# Schematic1.net
KiCad netlist of a schematic drawn in EAGLE
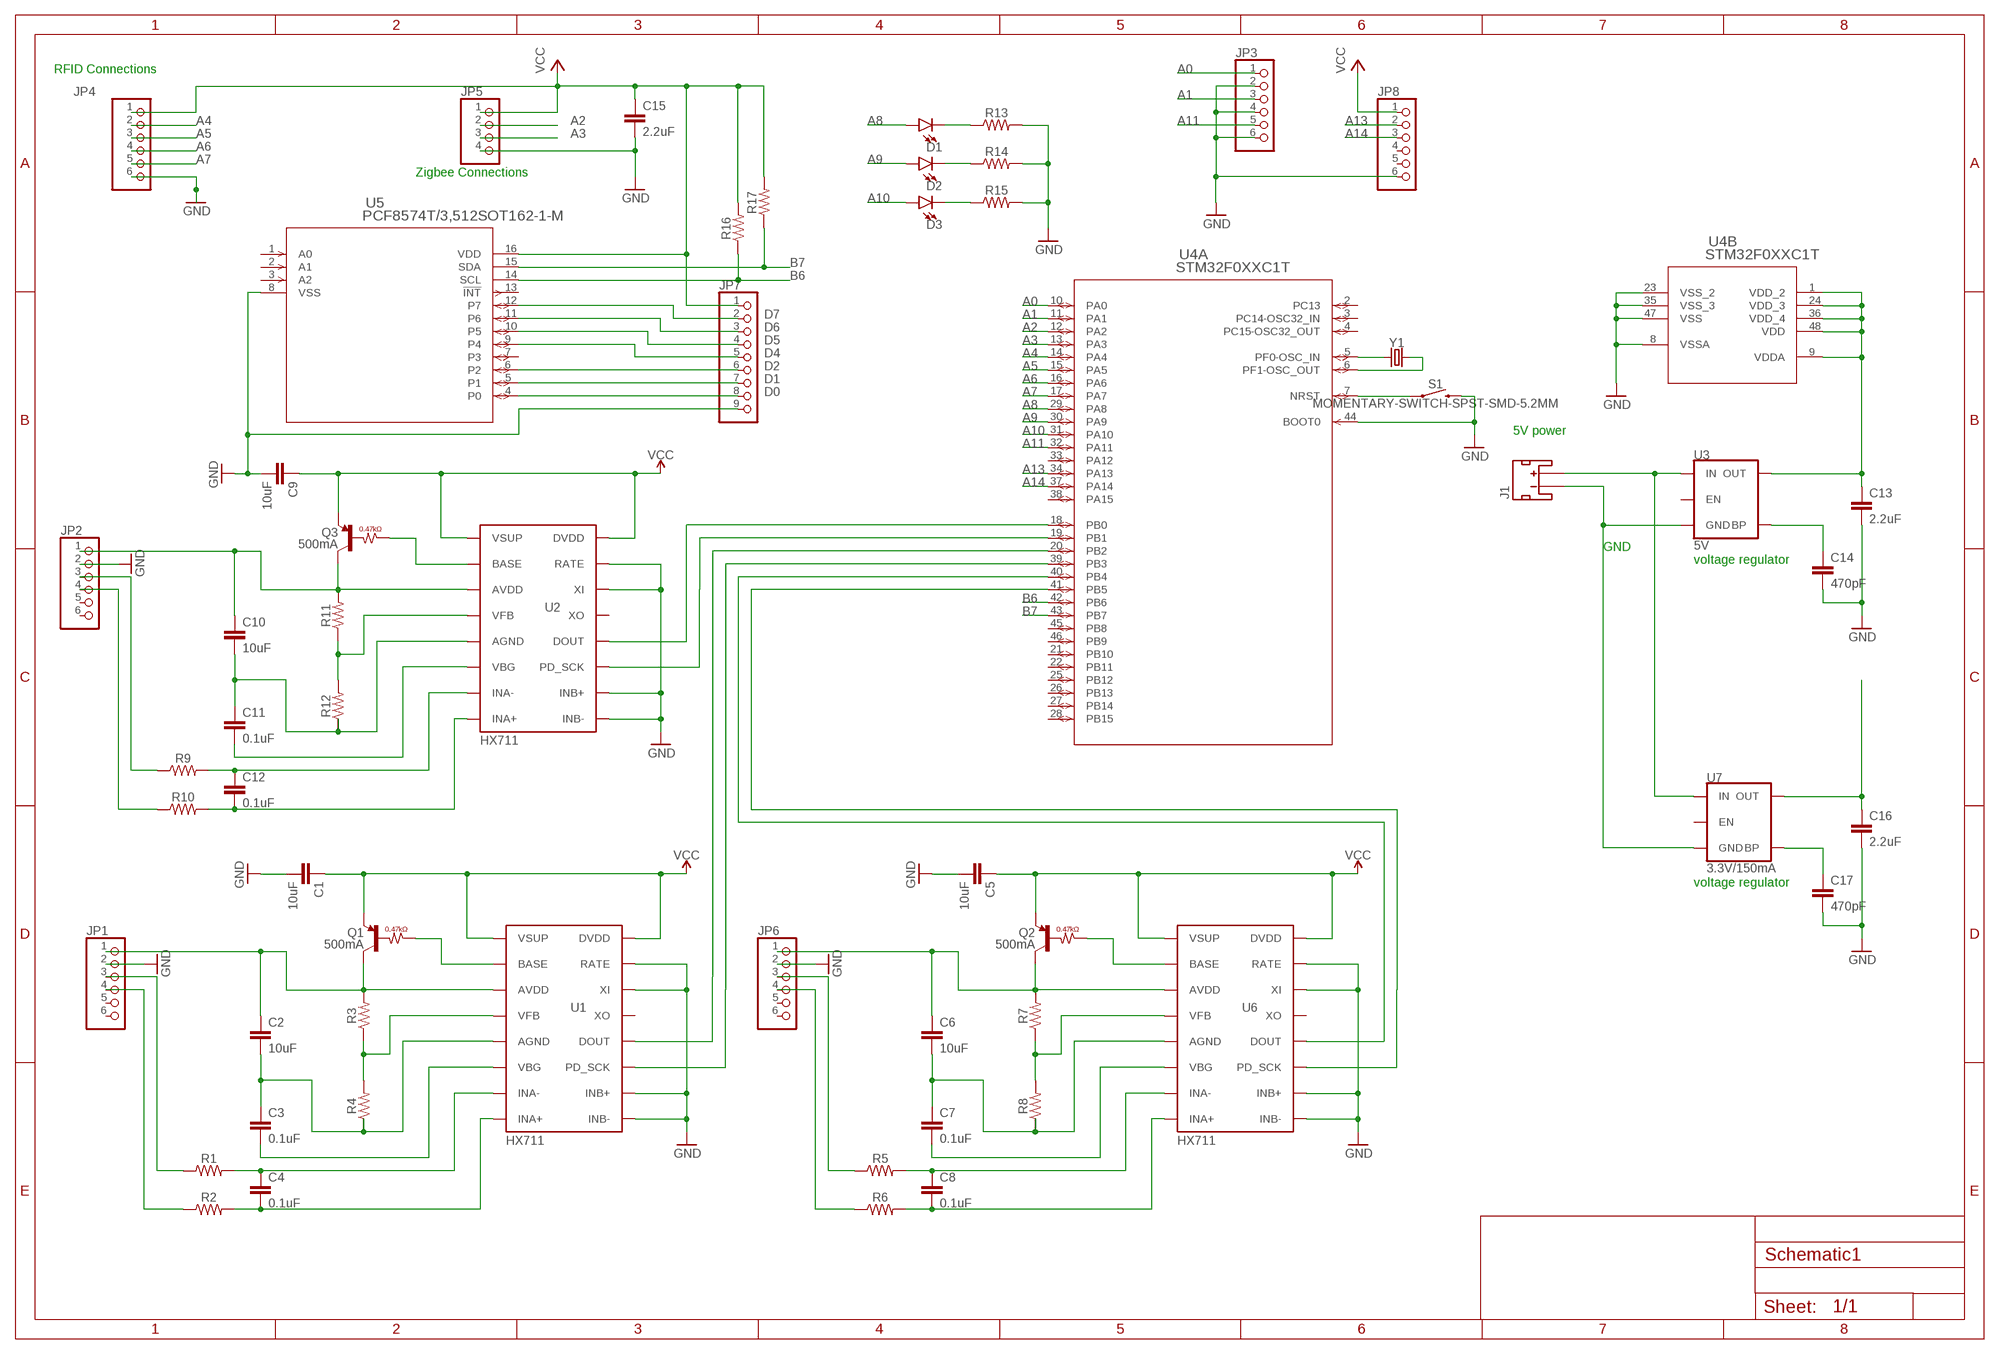
[diagram p0: schematic, sheet 1]

(export (version "E")
  (design (tool "Eeschema 10.0.6"))
  (components
    (comp (ref "C1")
      (value "10uF")
      (footprint "eagle-import:0603")
      (libsource (lib "eagle-import") (part "10UF-0603-6.3V-20%"))
    )
    (comp (ref "C2")
      (value "10uF")
      (footprint "eagle-import:0603")
      (libsource (lib "eagle-import") (part "10UF-0603-6.3V-20%"))
    )
    (comp (ref "C3")
      (value "0.1uF")
      (footprint "eagle-import:0603")
      (libsource (lib "eagle-import") (part "0.1UF-0603-25V-(+80/-20%)"))
    )
    (comp (ref "C4")
      (value "0.1uF")
      (footprint "eagle-import:0603")
      (libsource (lib "eagle-import") (part "0.1UF-0603-25V-(+80/-20%)"))
    )
    (comp (ref "C5")
      (value "10uF")
      (footprint "eagle-import:0603")
      (libsource (lib "eagle-import") (part "10UF-0603-6.3V-20%"))
    )
    (comp (ref "C6")
      (value "10uF")
      (footprint "eagle-import:0603")
      (libsource (lib "eagle-import") (part "10UF-0603-6.3V-20%"))
    )
    (comp (ref "C7")
      (value "0.1uF")
      (footprint "eagle-import:0603")
      (libsource (lib "eagle-import") (part "0.1UF-0603-25V-(+80/-20%)"))
    )
    (comp (ref "C8")
      (value "0.1uF")
      (footprint "eagle-import:0603")
      (libsource (lib "eagle-import") (part "0.1UF-0603-25V-(+80/-20%)"))
    )
    (comp (ref "C9")
      (value "10uF")
      (footprint "eagle-import:0603")
      (libsource (lib "eagle-import") (part "10UF-0603-6.3V-20%"))
    )
    (comp (ref "C10")
      (value "10uF")
      (footprint "eagle-import:0603")
      (libsource (lib "eagle-import") (part "10UF-0603-6.3V-20%"))
    )
    (comp (ref "C11")
      (value "0.1uF")
      (footprint "eagle-import:0603")
      (libsource (lib "eagle-import") (part "0.1UF-0603-25V-(+80/-20%)"))
    )
    (comp (ref "C12")
      (value "0.1uF")
      (footprint "eagle-import:0603")
      (libsource (lib "eagle-import") (part "0.1UF-0603-25V-(+80/-20%)"))
    )
    (comp (ref "C13")
      (value "2.2uF")
      (footprint "eagle-import:0603")
      (libsource (lib "eagle-import") (part "2.2UF-0603-10V-20%"))
    )
    (comp (ref "C14")
      (value "470pF")
      (footprint "eagle-import:0603")
      (libsource (lib "eagle-import") (part "470PF-0603-50V-5%"))
    )
    (comp (ref "C15")
      (value "2.2uF")
      (footprint "eagle-import:0603")
      (libsource (lib "eagle-import") (part "2.2UF-0603-10V-20%"))
    )
    (comp (ref "C16")
      (value "2.2uF")
      (footprint "eagle-import:0603")
      (libsource (lib "eagle-import") (part "2.2UF-0603-10V-20%"))
    )
    (comp (ref "C17")
      (value "470pF")
      (footprint "eagle-import:0603")
      (libsource (lib "eagle-import") (part "470PF-0603-50V-5%"))
    )
    (comp (ref "D1")
      (value "LED5MM")
      (footprint "eagle-import:LED_5MM")
      (libsource (lib "eagle-import") (part "LED5MM"))
    )
    (comp (ref "D2")
      (value "LED5MM")
      (footprint "eagle-import:LED_5MM")
      (libsource (lib "eagle-import") (part "LED5MM"))
    )
    (comp (ref "D3")
      (value "LED5MM")
      (footprint "eagle-import:LED_5MM")
      (libsource (lib "eagle-import") (part "LED5MM"))
    )
    (comp (ref "J1")
      (value "JST_2MM_MALE")
      (footprint "eagle-import:JST-2-SMD")
      (libsource (lib "eagle-import") (part "JST_2MM_MALE"))
    )
    (comp (ref "JP1")
      (value "PINHD-1X6")
      (footprint "eagle-import:1X06")
      (libsource (lib "eagle-import") (part "PINHD-1X6"))
    )
    (comp (ref "JP2")
      (value "PINHD-1X6")
      (footprint "eagle-import:1X06")
      (libsource (lib "eagle-import") (part "PINHD-1X6"))
    )
    (comp (ref "JP3")
      (value "PINHD-1X6")
      (footprint "eagle-import:1X06")
      (libsource (lib "eagle-import") (part "PINHD-1X6"))
    )
    (comp (ref "JP4")
      (value "PINHD-1X6")
      (footprint "eagle-import:1X06")
      (libsource (lib "eagle-import") (part "PINHD-1X6"))
    )
    (comp (ref "JP5")
      (value "PINHD-1X4")
      (footprint "eagle-import:1X04")
      (libsource (lib "eagle-import") (part "PINHD-1X4"))
    )
    (comp (ref "JP6")
      (value "PINHD-1X6")
      (footprint "eagle-import:1X06")
      (libsource (lib "eagle-import") (part "PINHD-1X6"))
    )
    (comp (ref "JP7")
      (value "PINHD-1X9")
      (footprint "eagle-import:1X09")
      (libsource (lib "eagle-import") (part "PINHD-1X9"))
    )
    (comp (ref "JP8")
      (value "PINHD-1X6")
      (footprint "eagle-import:1X06")
      (libsource (lib "eagle-import") (part "PINHD-1X6"))
    )
    (comp (ref "Q1")
      (value "500mA")
      (footprint "eagle-import:SOT23-3")
      (libsource (lib "eagle-import") (part "TRANS_PNP_RES-DDTB142TC"))
    )
    (comp (ref "Q2")
      (value "500mA")
      (footprint "eagle-import:SOT23-3")
      (libsource (lib "eagle-import") (part "TRANS_PNP_RES-DDTB142TC"))
    )
    (comp (ref "Q3")
      (value "500mA")
      (footprint "eagle-import:SOT23-3")
      (libsource (lib "eagle-import") (part "TRANS_PNP_RES-DDTB142TC"))
    )
    (comp (ref "R1")
      (value "RESISTOR0603")
      (footprint "eagle-import:0603")
      (libsource (lib "eagle-import") (part "RESISTOR0603"))
    )
    (comp (ref "R2")
      (value "RESISTOR0603")
      (footprint "eagle-import:0603")
      (libsource (lib "eagle-import") (part "RESISTOR0603"))
    )
    (comp (ref "R3")
      (value "RESISTOR0603")
      (footprint "eagle-import:0603")
      (libsource (lib "eagle-import") (part "RESISTOR0603"))
    )
    (comp (ref "R4")
      (value "RESISTOR0603")
      (footprint "eagle-import:0603")
      (libsource (lib "eagle-import") (part "RESISTOR0603"))
    )
    (comp (ref "R5")
      (value "RESISTOR0603")
      (footprint "eagle-import:0603")
      (libsource (lib "eagle-import") (part "RESISTOR0603"))
    )
    (comp (ref "R6")
      (value "RESISTOR0603")
      (footprint "eagle-import:0603")
      (libsource (lib "eagle-import") (part "RESISTOR0603"))
    )
    (comp (ref "R7")
      (value "RESISTOR0603")
      (footprint "eagle-import:0603")
      (libsource (lib "eagle-import") (part "RESISTOR0603"))
    )
    (comp (ref "R8")
      (value "RESISTOR0603")
      (footprint "eagle-import:0603")
      (libsource (lib "eagle-import") (part "RESISTOR0603"))
    )
    (comp (ref "R9")
      (value "RESISTOR0603")
      (footprint "eagle-import:0603")
      (libsource (lib "eagle-import") (part "RESISTOR0603"))
    )
    (comp (ref "R10")
      (value "RESISTOR0603")
      (footprint "eagle-import:0603")
      (libsource (lib "eagle-import") (part "RESISTOR0603"))
    )
    (comp (ref "R11")
      (value "RESISTOR0603")
      (footprint "eagle-import:0603")
      (libsource (lib "eagle-import") (part "RESISTOR0603"))
    )
    (comp (ref "R12")
      (value "RESISTOR0603")
      (footprint "eagle-import:0603")
      (libsource (lib "eagle-import") (part "RESISTOR0603"))
    )
    (comp (ref "R13")
      (value "RESISTOR0603")
      (footprint "eagle-import:0603")
      (libsource (lib "eagle-import") (part "RESISTOR0603"))
    )
    (comp (ref "R14")
      (value "RESISTOR0603")
      (footprint "eagle-import:0603")
      (libsource (lib "eagle-import") (part "RESISTOR0603"))
    )
    (comp (ref "R15")
      (value "RESISTOR0603")
      (footprint "eagle-import:0603")
      (libsource (lib "eagle-import") (part "RESISTOR0603"))
    )
    (comp (ref "R16")
      (value "RESISTOR0603")
      (footprint "eagle-import:0603")
      (libsource (lib "eagle-import") (part "RESISTOR0603"))
    )
    (comp (ref "R17")
      (value "RESISTOR0603")
      (footprint "eagle-import:0603")
      (libsource (lib "eagle-import") (part "RESISTOR0603"))
    )
    (comp (ref "S1")
      (value "MOMENTARY-SWITCH-SPST-SMD-5.2MM")
      (footprint "eagle-import:TACTILE_SWITCH_SMD_5.2MM")
      (libsource (lib "eagle-import") (part "MOMENTARY-SWITCH-SPST-SMD-5.2MM"))
    )
    (comp (ref "U1")
      (value "HX711")
      (footprint "eagle-import:SO16")
      (libsource (lib "eagle-import") (part "HX711"))
    )
    (comp (ref "U2")
      (value "HX711")
      (footprint "eagle-import:SO16")
      (libsource (lib "eagle-import") (part "HX711"))
    )
    (comp (ref "U3")
      (value "5V")
      (footprint "eagle-import:SOT23-5")
      (libsource (lib "eagle-import") (part "V_REG_MIC52055V"))
    )
    (comp (ref "U4")
      (value "STM32F0XXC1T")
      (footprint "eagle-import:LQFP48-7X7MM")
      (fields (field (name "MANUFACTURER_PART_NUMBER") "stm32f0xxc1t"))
      (libsource (lib "eagle-import") (part "STM32F0XXC1T"))
    )
    (comp (ref "U5")
      (value "PCF8574T/3,512SOT162-1-M")
      (footprint "eagle-import:SOT162-1-M")
      (fields (field (name "MANUFACTURER_PART_NUMBER") "PCF8574T3512"))
      (libsource (lib "eagle-import") (part "PCF8574T/3,512SOT162-1-M"))
    )
    (comp (ref "U6")
      (value "HX711")
      (footprint "eagle-import:SO16")
      (libsource (lib "eagle-import") (part "HX711"))
    )
    (comp (ref "U7")
      (value "3.3V/150mA")
      (footprint "eagle-import:SOT23-5")
      (libsource (lib "eagle-import") (part "V_REG_MIC52053.3V"))
    )
    (comp (ref "Y1")
      (value "CRYSTALPTH-HC49US")
      (footprint "eagle-import:HC49US")
      (libsource (lib "eagle-import") (part "CRYSTALPTH-HC49US"))
    )
  )
  (nets
    (net (code "1") (name "/A0") (class "Default")
      (node (ref "JP3") (pin "1") (pinfunction "1_1") (pintype "passive"))
      (node (ref "U4") (pin "10") (pinfunction "PA0_10") (pintype "bidirectional"))
    )
    (net (code "2") (name "/A1") (class "Default")
      (node (ref "JP3") (pin "3") (pinfunction "3_3") (pintype "passive"))
      (node (ref "U4") (pin "11") (pinfunction "PA1_11") (pintype "bidirectional"))
    )
    (net (code "3") (name "/A2") (class "Default")
      (node (ref "JP5") (pin "2") (pinfunction "2_2") (pintype "passive"))
      (node (ref "U4") (pin "12") (pinfunction "PA2_12") (pintype "bidirectional"))
    )
    (net (code "4") (name "/A3") (class "Default")
      (node (ref "JP5") (pin "3") (pinfunction "3_3") (pintype "passive"))
      (node (ref "U4") (pin "13") (pinfunction "PA3_13") (pintype "bidirectional"))
    )
    (net (code "5") (name "/A4") (class "Default")
      (node (ref "JP4") (pin "2") (pinfunction "2_2") (pintype "passive"))
      (node (ref "U4") (pin "14") (pinfunction "PA4_14") (pintype "bidirectional"))
    )
    (net (code "6") (name "/A5") (class "Default")
      (node (ref "JP4") (pin "3") (pinfunction "3_3") (pintype "passive"))
      (node (ref "U4") (pin "15") (pinfunction "PA5_15") (pintype "bidirectional"))
    )
    (net (code "7") (name "/A6") (class "Default")
      (node (ref "JP4") (pin "4") (pinfunction "4_4") (pintype "passive"))
      (node (ref "U4") (pin "16") (pinfunction "PA6_16") (pintype "bidirectional"))
    )
    (net (code "8") (name "/A7") (class "Default")
      (node (ref "JP4") (pin "5") (pinfunction "5_5") (pintype "passive"))
      (node (ref "U4") (pin "17") (pinfunction "PA7_17") (pintype "bidirectional"))
    )
    (net (code "9") (name "/A8") (class "Default")
      (node (ref "D1") (pin "A") (pinfunction "A_A") (pintype "passive"))
      (node (ref "U4") (pin "29") (pinfunction "PA8_29") (pintype "bidirectional"))
    )
    (net (code "10") (name "/A9") (class "Default")
      (node (ref "D2") (pin "A") (pinfunction "A_A") (pintype "passive"))
      (node (ref "U4") (pin "30") (pinfunction "PA9_30") (pintype "bidirectional"))
    )
    (net (code "11") (name "/A10") (class "Default")
      (node (ref "D3") (pin "A") (pinfunction "A_A") (pintype "passive"))
      (node (ref "U4") (pin "31") (pinfunction "PA10_31") (pintype "bidirectional"))
    )
    (net (code "12") (name "/A11") (class "Default")
      (node (ref "JP3") (pin "5") (pinfunction "5_5") (pintype "passive"))
      (node (ref "U4") (pin "32") (pinfunction "PA11_32") (pintype "bidirectional"))
    )
    (net (code "13") (name "/A13") (class "Default")
      (node (ref "JP8") (pin "2") (pinfunction "2_2") (pintype "passive"))
      (node (ref "U4") (pin "34") (pinfunction "PA13_34") (pintype "bidirectional"))
    )
    (net (code "14") (name "/A14") (class "Default")
      (node (ref "JP8") (pin "3") (pinfunction "3_3") (pintype "passive"))
      (node (ref "U4") (pin "37") (pinfunction "PA14_37") (pintype "bidirectional"))
    )
    (net (code "15") (name "/B6") (class "Default")
      (node (ref "R16") (pin "1") (pinfunction "1_1") (pintype "passive"))
      (node (ref "U4") (pin "42") (pinfunction "PB6_42") (pintype "bidirectional"))
      (node (ref "U5") (pin "14") (pinfunction "SCL_14") (pintype "passive"))
    )
    (net (code "16") (name "/B7") (class "Default")
      (node (ref "R17") (pin "1") (pinfunction "1_1") (pintype "passive"))
      (node (ref "U4") (pin "43") (pinfunction "PB7_43") (pintype "bidirectional"))
      (node (ref "U5") (pin "15") (pinfunction "SDA_15") (pintype "passive"))
    )
    (net (code "17") (name "/D0") (class "Default")
      (node (ref "JP7") (pin "8") (pinfunction "8_8") (pintype "passive"))
      (node (ref "U5") (pin "4") (pinfunction "P0_4") (pintype "bidirectional"))
    )
    (net (code "18") (name "/D1") (class "Default")
      (node (ref "JP7") (pin "7") (pinfunction "7_7") (pintype "passive"))
      (node (ref "U5") (pin "5") (pinfunction "P1_5") (pintype "bidirectional"))
    )
    (net (code "19") (name "/D2") (class "Default")
      (node (ref "JP7") (pin "6") (pinfunction "6_6") (pintype "passive"))
      (node (ref "U5") (pin "6") (pinfunction "P2_6") (pintype "bidirectional"))
    )
    (net (code "20") (name "/D4") (class "Default")
      (node (ref "JP7") (pin "5") (pinfunction "5_5") (pintype "passive"))
      (node (ref "U5") (pin "9") (pinfunction "P4_9") (pintype "bidirectional"))
    )
    (net (code "21") (name "/D5") (class "Default")
      (node (ref "JP7") (pin "4") (pinfunction "4_4") (pintype "passive"))
      (node (ref "U5") (pin "10") (pinfunction "P5_10") (pintype "bidirectional"))
    )
    (net (code "22") (name "/D6") (class "Default")
      (node (ref "JP7") (pin "3") (pinfunction "3_3") (pintype "passive"))
      (node (ref "U5") (pin "11") (pinfunction "P6_11") (pintype "bidirectional"))
    )
    (net (code "23") (name "/D7") (class "Default")
      (node (ref "JP7") (pin "2") (pinfunction "2_2") (pintype "passive"))
      (node (ref "U5") (pin "12") (pinfunction "P7_12") (pintype "bidirectional"))
    )
    (net (code "24") (name "GND") (class "Default")
      (node (ref "C1") (pin "2") (pinfunction "2_2") (pintype "passive"))
      (node (ref "C13") (pin "2") (pinfunction "2_2") (pintype "passive"))
      (node (ref "C14") (pin "2") (pinfunction "2_2") (pintype "passive"))
      (node (ref "C15") (pin "2") (pinfunction "2_2") (pintype "passive"))
      (node (ref "C16") (pin "2") (pinfunction "2_2") (pintype "passive"))
      (node (ref "C17") (pin "2") (pinfunction "2_2") (pintype "passive"))
      (node (ref "C5") (pin "2") (pinfunction "2_2") (pintype "passive"))
      (node (ref "C9") (pin "2") (pinfunction "2_2") (pintype "passive"))
      (node (ref "JP1") (pin "2") (pinfunction "2_2") (pintype "passive"))
      (node (ref "JP2") (pin "2") (pinfunction "2_2") (pintype "passive"))
      (node (ref "JP3") (pin "2") (pinfunction "2_2") (pintype "passive"))
      (node (ref "JP3") (pin "4") (pinfunction "4_4") (pintype "passive"))
      (node (ref "JP3") (pin "6") (pinfunction "6_6") (pintype "passive"))
      (node (ref "JP4") (pin "6") (pinfunction "6_6") (pintype "passive"))
      (node (ref "JP5") (pin "4") (pinfunction "4_4") (pintype "passive"))
      (node (ref "JP6") (pin "2") (pinfunction "2_2") (pintype "passive"))
      (node (ref "JP7") (pin "9") (pinfunction "9_9") (pintype "passive"))
      (node (ref "JP8") (pin "6") (pinfunction "6_6") (pintype "passive"))
      (node (ref "R13") (pin "2") (pinfunction "2_2") (pintype "passive"))
      (node (ref "R14") (pin "2") (pinfunction "2_2") (pintype "passive"))
      (node (ref "R15") (pin "2") (pinfunction "2_2") (pintype "passive"))
      (node (ref "S1") (pin "3") (pinfunction "2_3") (pintype "passive"))
      (node (ref "U1") (pin "10") (pinfunction "INB+_10") (pintype "bidirectional"))
      (node (ref "U1") (pin "14") (pinfunction "XI_14") (pintype "bidirectional"))
      (node (ref "U1") (pin "15") (pinfunction "RATE_15") (pintype "bidirectional"))
      (node (ref "U1") (pin "9") (pinfunction "INB-_9") (pintype "bidirectional"))
      (node (ref "U2") (pin "10") (pinfunction "INB+_10") (pintype "bidirectional"))
      (node (ref "U2") (pin "14") (pinfunction "XI_14") (pintype "bidirectional"))
      (node (ref "U2") (pin "15") (pinfunction "RATE_15") (pintype "bidirectional"))
      (node (ref "U2") (pin "9") (pinfunction "INB-_9") (pintype "bidirectional"))
      (node (ref "U4") (pin "23") (pinfunction "VSS_2_23") (pintype "power_in"))
      (node (ref "U4") (pin "35") (pinfunction "VSS_3_35") (pintype "power_in"))
      (node (ref "U4") (pin "44") (pinfunction "BOOT0_44") (pintype "input"))
      (node (ref "U4") (pin "47") (pinfunction "VSS_47") (pintype "power_in"))
      (node (ref "U4") (pin "8") (pinfunction "VSSA_8") (pintype "power_in"))
      (node (ref "U5") (pin "8") (pinfunction "VSS_8") (pintype "power_in"))
      (node (ref "U6") (pin "10") (pinfunction "INB+_10") (pintype "bidirectional"))
      (node (ref "U6") (pin "14") (pinfunction "XI_14") (pintype "bidirectional"))
      (node (ref "U6") (pin "15") (pinfunction "RATE_15") (pintype "bidirectional"))
      (node (ref "U6") (pin "9") (pinfunction "INB-_9") (pintype "bidirectional"))
    )
    (net (code "25") (name "Net-(D1-C)") (class "Default")
      (node (ref "D1") (pin "K") (pinfunction "C_K") (pintype "passive"))
      (node (ref "R13") (pin "1") (pinfunction "1_1") (pintype "passive"))
    )
    (net (code "26") (name "Net-(D2-C)") (class "Default")
      (node (ref "D2") (pin "K") (pinfunction "C_K") (pintype "passive"))
      (node (ref "R14") (pin "1") (pinfunction "1_1") (pintype "passive"))
    )
    (net (code "27") (name "Net-(D3-C)") (class "Default")
      (node (ref "D3") (pin "K") (pinfunction "C_K") (pintype "passive"))
      (node (ref "R15") (pin "1") (pinfunction "1_1") (pintype "passive"))
    )
    (net (code "28") (name "Net-(J1-+)") (class "Default")
      (node (ref "J1") (pin "2") (pinfunction "+_2") (pintype "bidirectional"))
      (node (ref "U3") (pin "1") (pinfunction "IN_1") (pintype "input"))
      (node (ref "U7") (pin "1") (pinfunction "IN_1") (pintype "input"))
    )
    (net (code "29") (name "Net-(J1--)") (class "Default")
      (node (ref "J1") (pin "1") (pinfunction "-_1") (pintype "bidirectional"))
      (node (ref "U3") (pin "2") (pinfunction "GND_2") (pintype "input"))
      (node (ref "U7") (pin "2") (pinfunction "GND_2") (pintype "input"))
    )
    (net (code "30") (name "Net-(JP1-Pad3)") (class "Default")
      (node (ref "JP1") (pin "3") (pinfunction "3_3") (pintype "passive"))
      (node (ref "R1") (pin "1") (pinfunction "1_1") (pintype "passive"))
    )
    (net (code "31") (name "Net-(JP1-Pad4)") (class "Default")
      (node (ref "JP1") (pin "4") (pinfunction "4_4") (pintype "passive"))
      (node (ref "R2") (pin "1") (pinfunction "1_1") (pintype "passive"))
    )
    (net (code "32") (name "Net-(JP2-Pad3)") (class "Default")
      (node (ref "JP2") (pin "3") (pinfunction "3_3") (pintype "passive"))
      (node (ref "R9") (pin "1") (pinfunction "1_1") (pintype "passive"))
    )
    (net (code "33") (name "Net-(JP2-Pad4)") (class "Default")
      (node (ref "JP2") (pin "4") (pinfunction "4_4") (pintype "passive"))
      (node (ref "R10") (pin "1") (pinfunction "1_1") (pintype "passive"))
    )
    (net (code "34") (name "Net-(JP6-Pad3)") (class "Default")
      (node (ref "JP6") (pin "3") (pinfunction "3_3") (pintype "passive"))
      (node (ref "R5") (pin "1") (pinfunction "1_1") (pintype "passive"))
    )
    (net (code "35") (name "Net-(JP6-Pad4)") (class "Default")
      (node (ref "JP6") (pin "4") (pinfunction "4_4") (pintype "passive"))
      (node (ref "R6") (pin "1") (pinfunction "1_1") (pintype "passive"))
    )
    (net (code "36") (name "Net-(Q1-B)") (class "Default")
      (node (ref "Q1") (pin "1") (pinfunction "B_1") (pintype "passive"))
      (node (ref "U1") (pin "2") (pinfunction "BASE_2") (pintype "bidirectional"))
    )
    (net (code "37") (name "Net-(Q1-C)") (class "Default")
      (node (ref "C2") (pin "1") (pinfunction "1_1") (pintype "passive"))
      (node (ref "JP1") (pin "1") (pinfunction "1_1") (pintype "passive"))
      (node (ref "Q1") (pin "3") (pinfunction "C_3") (pintype "passive"))
      (node (ref "R3") (pin "2") (pinfunction "2_2") (pintype "passive"))
      (node (ref "U1") (pin "3") (pinfunction "AVDD_3") (pintype "bidirectional"))
    )
    (net (code "38") (name "Net-(Q2-B)") (class "Default")
      (node (ref "Q2") (pin "1") (pinfunction "B_1") (pintype "passive"))
      (node (ref "U6") (pin "2") (pinfunction "BASE_2") (pintype "bidirectional"))
    )
    (net (code "39") (name "Net-(Q2-C)") (class "Default")
      (node (ref "C6") (pin "1") (pinfunction "1_1") (pintype "passive"))
      (node (ref "JP6") (pin "1") (pinfunction "1_1") (pintype "passive"))
      (node (ref "Q2") (pin "3") (pinfunction "C_3") (pintype "passive"))
      (node (ref "R7") (pin "2") (pinfunction "2_2") (pintype "passive"))
      (node (ref "U6") (pin "3") (pinfunction "AVDD_3") (pintype "bidirectional"))
    )
    (net (code "40") (name "Net-(Q3-B)") (class "Default")
      (node (ref "Q3") (pin "1") (pinfunction "B_1") (pintype "passive"))
      (node (ref "U2") (pin "2") (pinfunction "BASE_2") (pintype "bidirectional"))
    )
    (net (code "41") (name "Net-(Q3-C)") (class "Default")
      (node (ref "C10") (pin "1") (pinfunction "1_1") (pintype "passive"))
      (node (ref "JP2") (pin "1") (pinfunction "1_1") (pintype "passive"))
      (node (ref "Q3") (pin "3") (pinfunction "C_3") (pintype "passive"))
      (node (ref "R11") (pin "2") (pinfunction "2_2") (pintype "passive"))
      (node (ref "U2") (pin "3") (pinfunction "AVDD_3") (pintype "bidirectional"))
    )
    (net (code "42") (name "Net-(U1-AGND)") (class "Default")
      (node (ref "C2") (pin "2") (pinfunction "2_2") (pintype "passive"))
      (node (ref "C3") (pin "1") (pinfunction "1_1") (pintype "passive"))
      (node (ref "R4") (pin "1") (pinfunction "1_1") (pintype "passive"))
      (node (ref "U1") (pin "5") (pinfunction "AGND_5") (pintype "bidirectional"))
    )
    (net (code "43") (name "Net-(U1-DOUT)") (class "Default")
      (node (ref "U1") (pin "12") (pinfunction "DOUT_12") (pintype "bidirectional"))
      (node (ref "U4") (pin "20") (pinfunction "PB2_20") (pintype "bidirectional"))
    )
    (net (code "44") (name "Net-(U1-INA+)") (class "Default")
      (node (ref "C4") (pin "2") (pinfunction "2_2") (pintype "passive"))
      (node (ref "R2") (pin "2") (pinfunction "2_2") (pintype "passive"))
      (node (ref "U1") (pin "8") (pinfunction "INA+_8") (pintype "bidirectional"))
    )
    (net (code "45") (name "Net-(U1-INA-)") (class "Default")
      (node (ref "C4") (pin "1") (pinfunction "1_1") (pintype "passive"))
      (node (ref "R1") (pin "2") (pinfunction "2_2") (pintype "passive"))
      (node (ref "U1") (pin "7") (pinfunction "INA-_7") (pintype "bidirectional"))
    )
    (net (code "46") (name "Net-(U1-PD_SCK)") (class "Default")
      (node (ref "U1") (pin "11") (pinfunction "PD_SCK_11") (pintype "bidirectional"))
      (node (ref "U4") (pin "39") (pinfunction "PB3_39") (pintype "bidirectional"))
    )
    (net (code "47") (name "Net-(U1-VBG)") (class "Default")
      (node (ref "C3") (pin "2") (pinfunction "2_2") (pintype "passive"))
      (node (ref "U1") (pin "6") (pinfunction "VBG_6") (pintype "bidirectional"))
    )
    (net (code "48") (name "Net-(U1-VFB)") (class "Default")
      (node (ref "R3") (pin "1") (pinfunction "1_1") (pintype "passive"))
      (node (ref "R4") (pin "2") (pinfunction "2_2") (pintype "passive"))
      (node (ref "U1") (pin "4") (pinfunction "VFB_4") (pintype "bidirectional"))
    )
    (net (code "49") (name "Net-(U2-AGND)") (class "Default")
      (node (ref "C10") (pin "2") (pinfunction "2_2") (pintype "passive"))
      (node (ref "C11") (pin "1") (pinfunction "1_1") (pintype "passive"))
      (node (ref "R12") (pin "1") (pinfunction "1_1") (pintype "passive"))
      (node (ref "U2") (pin "5") (pinfunction "AGND_5") (pintype "bidirectional"))
    )
    (net (code "50") (name "Net-(U2-DOUT)") (class "Default")
      (node (ref "U2") (pin "12") (pinfunction "DOUT_12") (pintype "bidirectional"))
      (node (ref "U4") (pin "18") (pinfunction "PB0_18") (pintype "bidirectional"))
    )
    (net (code "51") (name "Net-(U2-INA+)") (class "Default")
      (node (ref "C12") (pin "2") (pinfunction "2_2") (pintype "passive"))
      (node (ref "R10") (pin "2") (pinfunction "2_2") (pintype "passive"))
      (node (ref "U2") (pin "8") (pinfunction "INA+_8") (pintype "bidirectional"))
    )
    (net (code "52") (name "Net-(U2-INA-)") (class "Default")
      (node (ref "C12") (pin "1") (pinfunction "1_1") (pintype "passive"))
      (node (ref "R9") (pin "2") (pinfunction "2_2") (pintype "passive"))
      (node (ref "U2") (pin "7") (pinfunction "INA-_7") (pintype "bidirectional"))
    )
    (net (code "53") (name "Net-(U2-PD_SCK)") (class "Default")
      (node (ref "U2") (pin "11") (pinfunction "PD_SCK_11") (pintype "bidirectional"))
      (node (ref "U4") (pin "19") (pinfunction "PB1_19") (pintype "bidirectional"))
    )
    (net (code "54") (name "Net-(U2-VBG)") (class "Default")
      (node (ref "C11") (pin "2") (pinfunction "2_2") (pintype "passive"))
      (node (ref "U2") (pin "6") (pinfunction "VBG_6") (pintype "bidirectional"))
    )
    (net (code "55") (name "Net-(U2-VFB)") (class "Default")
      (node (ref "R11") (pin "1") (pinfunction "1_1") (pintype "passive"))
      (node (ref "R12") (pin "2") (pinfunction "2_2") (pintype "passive"))
      (node (ref "U2") (pin "4") (pinfunction "VFB_4") (pintype "bidirectional"))
    )
    (net (code "56") (name "Net-(U3-BP)") (class "Default")
      (node (ref "C14") (pin "1") (pinfunction "1_1") (pintype "passive"))
      (node (ref "U3") (pin "4") (pinfunction "BP_4") (pintype "input"))
    )
    (net (code "57") (name "Net-(U3-OUT)") (class "Default")
      (node (ref "C13") (pin "1") (pinfunction "1_1") (pintype "passive"))
      (node (ref "U3") (pin "5") (pinfunction "OUT_5") (pintype "passive"))
      (node (ref "U4") (pin "1") (pinfunction "VDD_2_1") (pintype "power_in"))
      (node (ref "U4") (pin "24") (pinfunction "VDD_3_24") (pintype "power_in"))
      (node (ref "U4") (pin "36") (pinfunction "VDD_4_36") (pintype "power_in"))
      (node (ref "U4") (pin "48") (pinfunction "VDD_48") (pintype "power_in"))
      (node (ref "U4") (pin "9") (pinfunction "VDDA_9") (pintype "power_in"))
    )
    (net (code "58") (name "Net-(U4A-NRST)") (class "Default")
      (node (ref "S1") (pin "1") (pinfunction "1_1") (pintype "passive"))
      (node (ref "U4") (pin "7") (pinfunction "NRST_7") (pintype "bidirectional"))
    )
    (net (code "59") (name "Net-(U4A-PB4)") (class "Default")
      (node (ref "U4") (pin "40") (pinfunction "PB4_40") (pintype "bidirectional"))
      (node (ref "U6") (pin "12") (pinfunction "DOUT_12") (pintype "bidirectional"))
    )
    (net (code "60") (name "Net-(U4A-PB5)") (class "Default")
      (node (ref "U4") (pin "41") (pinfunction "PB5_41") (pintype "bidirectional"))
      (node (ref "U6") (pin "11") (pinfunction "PD_SCK_11") (pintype "bidirectional"))
    )
    (net (code "61") (name "Net-(U4A-PF0-OSC_IN)") (class "Default")
      (node (ref "U4") (pin "5") (pinfunction "PF0-OSC_IN_5") (pintype "bidirectional"))
      (node (ref "Y1") (pin "1") (pinfunction "1_1") (pintype "passive"))
    )
    (net (code "62") (name "Net-(U4A-PF1-OSC_OUT)") (class "Default")
      (node (ref "U4") (pin "6") (pinfunction "PF1-OSC_OUT_6") (pintype "bidirectional"))
      (node (ref "Y1") (pin "2") (pinfunction "2_2") (pintype "passive"))
    )
    (net (code "63") (name "Net-(U6-AGND)") (class "Default")
      (node (ref "C6") (pin "2") (pinfunction "2_2") (pintype "passive"))
      (node (ref "C7") (pin "1") (pinfunction "1_1") (pintype "passive"))
      (node (ref "R8") (pin "1") (pinfunction "1_1") (pintype "passive"))
      (node (ref "U6") (pin "5") (pinfunction "AGND_5") (pintype "bidirectional"))
    )
    (net (code "64") (name "Net-(U6-INA+)") (class "Default")
      (node (ref "C8") (pin "2") (pinfunction "2_2") (pintype "passive"))
      (node (ref "R6") (pin "2") (pinfunction "2_2") (pintype "passive"))
      (node (ref "U6") (pin "8") (pinfunction "INA+_8") (pintype "bidirectional"))
    )
    (net (code "65") (name "Net-(U6-INA-)") (class "Default")
      (node (ref "C8") (pin "1") (pinfunction "1_1") (pintype "passive"))
      (node (ref "R5") (pin "2") (pinfunction "2_2") (pintype "passive"))
      (node (ref "U6") (pin "7") (pinfunction "INA-_7") (pintype "bidirectional"))
    )
    (net (code "66") (name "Net-(U6-VBG)") (class "Default")
      (node (ref "C7") (pin "2") (pinfunction "2_2") (pintype "passive"))
      (node (ref "U6") (pin "6") (pinfunction "VBG_6") (pintype "bidirectional"))
    )
    (net (code "67") (name "Net-(U6-VFB)") (class "Default")
      (node (ref "R7") (pin "1") (pinfunction "1_1") (pintype "passive"))
      (node (ref "R8") (pin "2") (pinfunction "2_2") (pintype "passive"))
      (node (ref "U6") (pin "4") (pinfunction "VFB_4") (pintype "bidirectional"))
    )
    (net (code "68") (name "Net-(U7-BP)") (class "Default")
      (node (ref "C17") (pin "1") (pinfunction "1_1") (pintype "passive"))
      (node (ref "U7") (pin "4") (pinfunction "BP_4") (pintype "input"))
    )
    (net (code "69") (name "Net-(U7-OUT)") (class "Default")
      (node (ref "C16") (pin "1") (pinfunction "1_1") (pintype "passive"))
      (node (ref "U7") (pin "5") (pinfunction "OUT_5") (pintype "passive"))
    )
    (net (code "70") (name "VCC") (class "Default")
      (node (ref "C1") (pin "1") (pinfunction "1_1") (pintype "passive"))
      (node (ref "C15") (pin "1") (pinfunction "1_1") (pintype "passive"))
      (node (ref "C5") (pin "1") (pinfunction "1_1") (pintype "passive"))
      (node (ref "C9") (pin "1") (pinfunction "1_1") (pintype "passive"))
      (node (ref "JP4") (pin "1") (pinfunction "1_1") (pintype "passive"))
      (node (ref "JP5") (pin "1") (pinfunction "1_1") (pintype "passive"))
      (node (ref "JP7") (pin "1") (pinfunction "1_1") (pintype "passive"))
      (node (ref "JP8") (pin "1") (pinfunction "1_1") (pintype "passive"))
      (node (ref "Q1") (pin "2") (pinfunction "E_2") (pintype "passive"))
      (node (ref "Q2") (pin "2") (pinfunction "E_2") (pintype "passive"))
      (node (ref "Q3") (pin "2") (pinfunction "E_2") (pintype "passive"))
      (node (ref "R16") (pin "2") (pinfunction "2_2") (pintype "passive"))
      (node (ref "R17") (pin "2") (pinfunction "2_2") (pintype "passive"))
      (node (ref "U1") (pin "1") (pinfunction "VSUP_1") (pintype "bidirectional"))
      (node (ref "U1") (pin "16") (pinfunction "DVDD_16") (pintype "bidirectional"))
      (node (ref "U2") (pin "1") (pinfunction "VSUP_1") (pintype "bidirectional"))
      (node (ref "U2") (pin "16") (pinfunction "DVDD_16") (pintype "bidirectional"))
      (node (ref "U5") (pin "16") (pinfunction "VDD_16") (pintype "power_in"))
      (node (ref "U6") (pin "1") (pinfunction "VSUP_1") (pintype "bidirectional"))
      (node (ref "U6") (pin "16") (pinfunction "DVDD_16") (pintype "bidirectional"))
    )
    (net (code "71") (name "unconnected-(J1-PAD1-PadNC1)") (class "Default")
      (node (ref "J1") (pin "NC1") (pinfunction "PAD1_NC1") (pintype "bidirectional"))
    )
    (net (code "72") (name "unconnected-(J1-PAD2-PadNC2)") (class "Default")
      (node (ref "J1") (pin "NC2") (pinfunction "PAD2_NC2") (pintype "bidirectional"))
    )
    (net (code "73") (name "unconnected-(JP1-Pad5)") (class "Default")
      (node (ref "JP1") (pin "5") (pinfunction "5_5") (pintype "passive"))
    )
    (net (code "74") (name "unconnected-(JP1-Pad6)") (class "Default")
      (node (ref "JP1") (pin "6") (pinfunction "6_6") (pintype "passive"))
    )
    (net (code "75") (name "unconnected-(JP2-Pad5)") (class "Default")
      (node (ref "JP2") (pin "5") (pinfunction "5_5") (pintype "passive"))
    )
    (net (code "76") (name "unconnected-(JP2-Pad6)") (class "Default")
      (node (ref "JP2") (pin "6") (pinfunction "6_6") (pintype "passive"))
    )
    (net (code "77") (name "unconnected-(JP6-Pad5)") (class "Default")
      (node (ref "JP6") (pin "5") (pinfunction "5_5") (pintype "passive"))
    )
    (net (code "78") (name "unconnected-(JP6-Pad6)") (class "Default")
      (node (ref "JP6") (pin "6") (pinfunction "6_6") (pintype "passive"))
    )
    (net (code "79") (name "unconnected-(JP8-Pad4)") (class "Default")
      (node (ref "JP8") (pin "4") (pinfunction "4_4") (pintype "passive"))
    )
    (net (code "80") (name "unconnected-(JP8-Pad5)") (class "Default")
      (node (ref "JP8") (pin "5") (pinfunction "5_5") (pintype "passive"))
    )
    (net (code "81") (name "unconnected-(U1-XO-Pad13)") (class "Default")
      (node (ref "U1") (pin "13") (pinfunction "XO_13") (pintype "bidirectional"))
    )
    (net (code "82") (name "unconnected-(U2-XO-Pad13)") (class "Default")
      (node (ref "U2") (pin "13") (pinfunction "XO_13") (pintype "bidirectional"))
    )
    (net (code "83") (name "unconnected-(U3-EN-Pad3)") (class "Default")
      (node (ref "U3") (pin "3") (pinfunction "EN_3") (pintype "input"))
    )
    (net (code "84") (name "unconnected-(U4A-PA12-Pad33)") (class "Default")
      (node (ref "U4") (pin "33") (pinfunction "PA12_33") (pintype "bidirectional"))
    )
    (net (code "85") (name "unconnected-(U4A-PA15-Pad38)") (class "Default")
      (node (ref "U4") (pin "38") (pinfunction "PA15_38") (pintype "bidirectional"))
    )
    (net (code "86") (name "unconnected-(U4A-PB8-Pad45)") (class "Default")
      (node (ref "U4") (pin "45") (pinfunction "PB8_45") (pintype "bidirectional"))
    )
    (net (code "87") (name "unconnected-(U4A-PB9-Pad46)") (class "Default")
      (node (ref "U4") (pin "46") (pinfunction "PB9_46") (pintype "bidirectional"))
    )
    (net (code "88") (name "unconnected-(U4A-PB10-Pad21)") (class "Default")
      (node (ref "U4") (pin "21") (pinfunction "PB10_21") (pintype "bidirectional"))
    )
    (net (code "89") (name "unconnected-(U4A-PB11-Pad22)") (class "Default")
      (node (ref "U4") (pin "22") (pinfunction "PB11_22") (pintype "bidirectional"))
    )
    (net (code "90") (name "unconnected-(U4A-PB12-Pad25)") (class "Default")
      (node (ref "U4") (pin "25") (pinfunction "PB12_25") (pintype "bidirectional"))
    )
    (net (code "91") (name "unconnected-(U4A-PB13-Pad26)") (class "Default")
      (node (ref "U4") (pin "26") (pinfunction "PB13_26") (pintype "bidirectional"))
    )
    (net (code "92") (name "unconnected-(U4A-PB14-Pad27)") (class "Default")
      (node (ref "U4") (pin "27") (pinfunction "PB14_27") (pintype "bidirectional"))
    )
    (net (code "93") (name "unconnected-(U4A-PB15-Pad28)") (class "Default")
      (node (ref "U4") (pin "28") (pinfunction "PB15_28") (pintype "bidirectional"))
    )
    (net (code "94") (name "unconnected-(U4A-PC13-Pad2)") (class "Default")
      (node (ref "U4") (pin "2") (pinfunction "PC13_2") (pintype "bidirectional"))
    )
    (net (code "95") (name "unconnected-(U4A-PC14-OSC32_IN-Pad3)") (class "Default")
      (node (ref "U4") (pin "3") (pinfunction "PC14-OSC32_IN_3") (pintype "bidirectional"))
    )
    (net (code "96") (name "unconnected-(U4A-PC15-OSC32_OUT-Pad4)") (class "Default")
      (node (ref "U4") (pin "4") (pinfunction "PC15-OSC32_OUT_4") (pintype "bidirectional"))
    )
    (net (code "97") (name "unconnected-(U5-A0-Pad1)") (class "Default")
      (node (ref "U5") (pin "1") (pinfunction "A0_1") (pintype "input"))
    )
    (net (code "98") (name "unconnected-(U5-A1-Pad2)") (class "Default")
      (node (ref "U5") (pin "2") (pinfunction "A1_2") (pintype "input"))
    )
    (net (code "99") (name "unconnected-(U5-A2-Pad3)") (class "Default")
      (node (ref "U5") (pin "3") (pinfunction "A2_3") (pintype "input"))
    )
    (net (code "100") (name "unconnected-(U5-P3-Pad7)") (class "Default")
      (node (ref "U5") (pin "7") (pinfunction "P3_7") (pintype "bidirectional"))
    )
    (net (code "101") (name "unconnected-(U5-~{INT}-Pad13)") (class "Default")
      (node (ref "U5") (pin "13") (pinfunction "~{INT}_13") (pintype "output"))
    )
    (net (code "102") (name "unconnected-(U6-XO-Pad13)") (class "Default")
      (node (ref "U6") (pin "13") (pinfunction "XO_13") (pintype "bidirectional"))
    )
    (net (code "103") (name "unconnected-(U7-EN-Pad3)") (class "Default")
      (node (ref "U7") (pin "3") (pinfunction "EN_3") (pintype "input"))
    )
  )
)
